# ESB32_with_USBC.net
KiCad netlist of a schematic drawn in Altium Designer
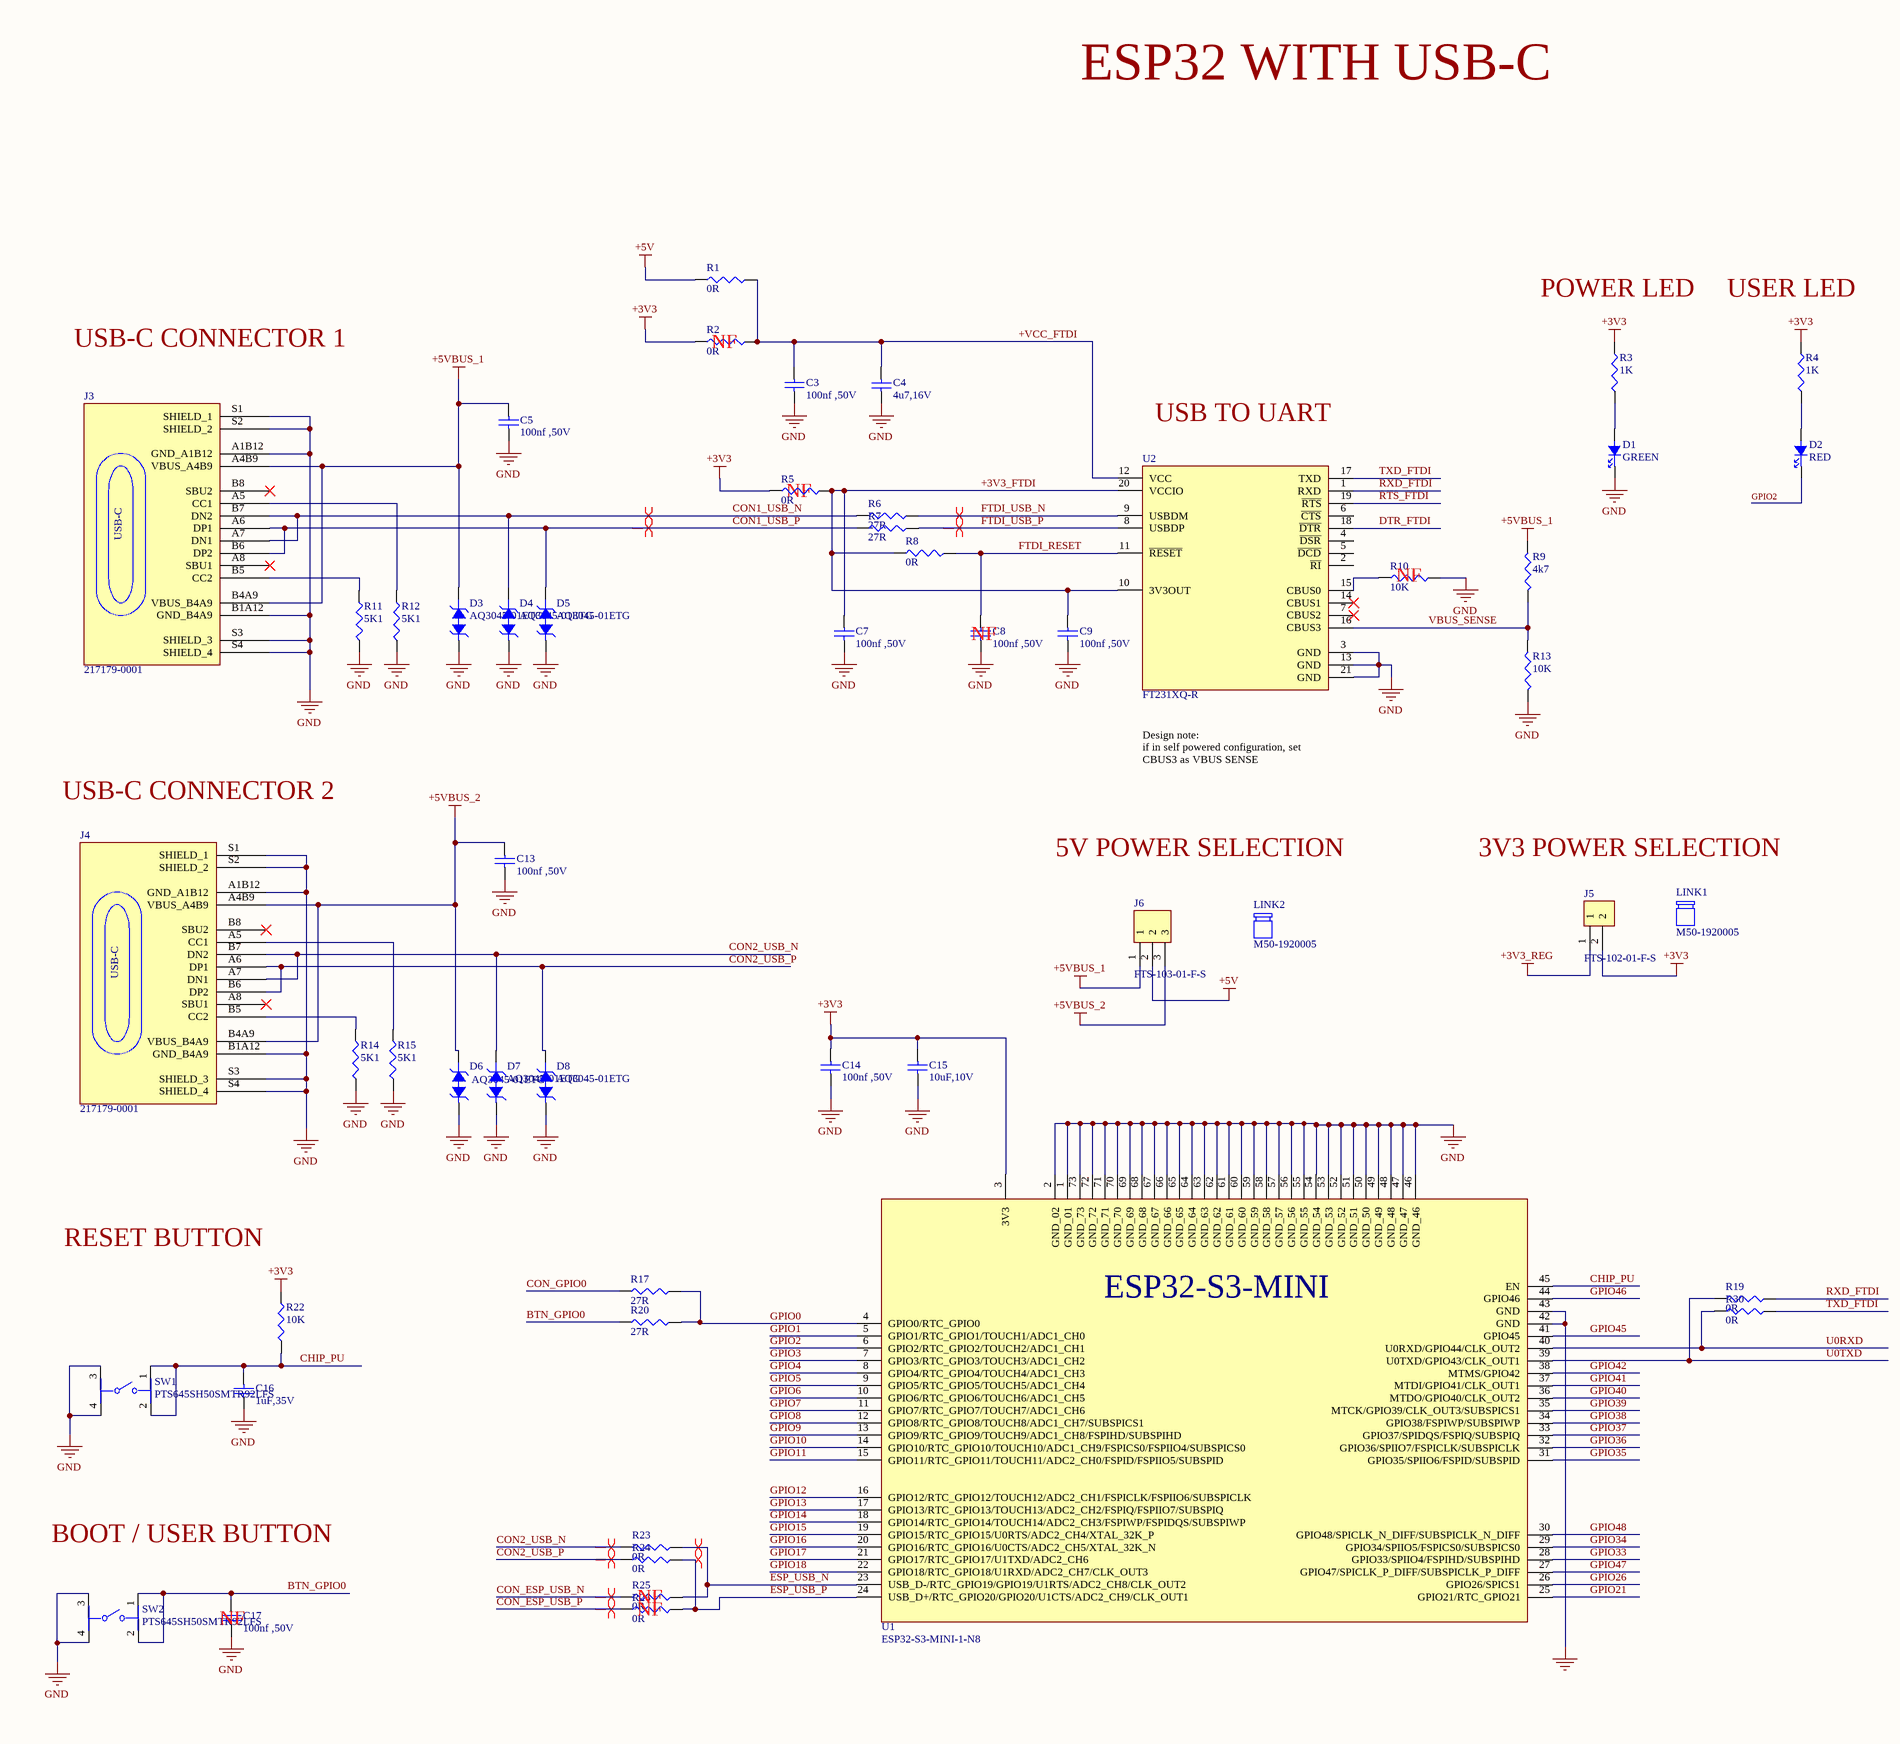
[diagram p0: ESB32 with USBC.SchDoc, left]
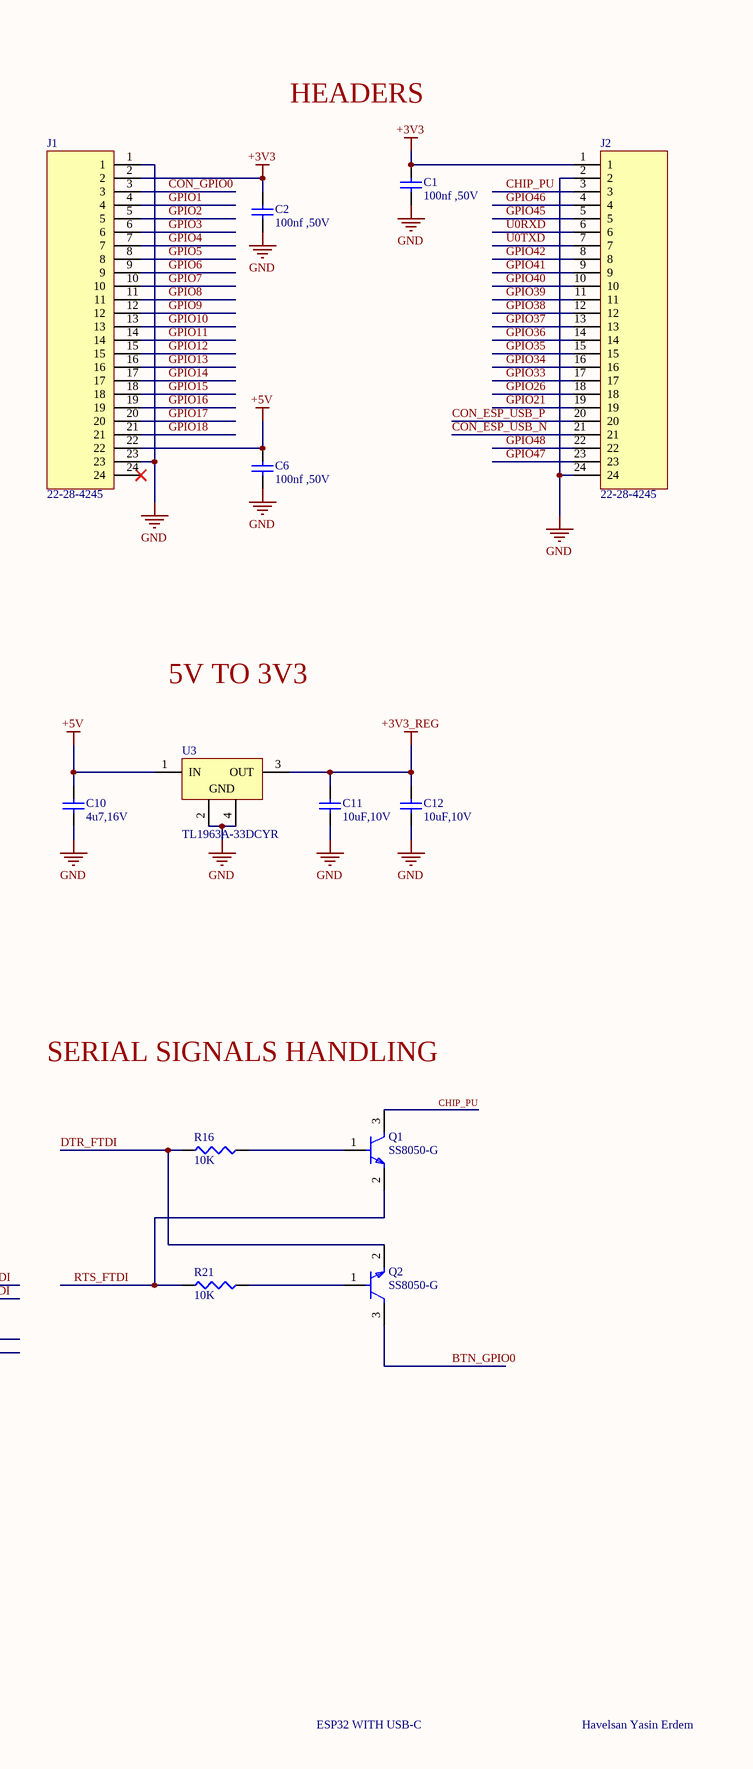
[diagram p1: ESB32 with USBC.SchDoc, right]

(export (version "E")
  (design (tool "Eeschema 10.0.6"))
  (components
    (comp (ref "C1")
      (value "100nf ,50V")
      (footprint "CAPC1005X55N")
      (description "CAP CER 0.1UF 50V X7R 0402")
      (fields
        (field (name "MANUFACTURER") "Samsung")
        (field (name "MANUFACTURER PART NUMBER") "CL05B104KB54PNC")
      )
      (libsource (lib "Schlib") (part "CL05B104KB54PNC"))
    )
    (comp (ref "C2")
      (value "100nf ,50V")
      (footprint "CAPC1005X55N")
      (description "CAP CER 0.1UF 50V X7R 0402")
      (fields
        (field (name "MANUFACTURER") "Samsung")
        (field (name "MANUFACTURER PART NUMBER") "CL05B104KB54PNC")
      )
      (libsource (lib "Schlib") (part "CL05B104KB54PNC"))
    )
    (comp (ref "C3")
      (value "100nf ,50V")
      (footprint "CAPC1005X55N")
      (description "CAP CER 0.1UF 50V X7R 0402")
      (fields
        (field (name "MANUFACTURER") "Samsung")
        (field (name "MANUFACTURER PART NUMBER") "CL05B104KB54PNC")
      )
      (libsource (lib "Schlib") (part "CL05B104KB54PNC"))
    )
    (comp (ref "C4")
      (value "4u7,16V")
      (footprint "CAPC1005X55N")
      (description "CAP CER 4.7UF 16V X5R 0402")
      (fields
        (field (name "MANUFACTURER") "Samsung")
        (field (name "MANUFACTURER PART NUMBER") "CL05A475MO5NUNC")
      )
      (libsource (lib "Schlib") (part "CL05A475MO5NUNC"))
    )
    (comp (ref "C5")
      (value "100nf ,50V")
      (footprint "CAPC1005X55N")
      (description "CAP CER 0.1UF 50V X7R 0402")
      (fields
        (field (name "MANUFACTURER") "Samsung")
        (field (name "MANUFACTURER PART NUMBER") "CL05B104KB54PNC")
      )
      (libsource (lib "Schlib") (part "CL05B104KB54PNC"))
    )
    (comp (ref "C6")
      (value "100nf ,50V")
      (footprint "CAPC1005X55N")
      (description "CAP CER 0.1UF 50V X7R 0402")
      (fields
        (field (name "MANUFACTURER") "Samsung")
        (field (name "MANUFACTURER PART NUMBER") "CL05B104KB54PNC")
      )
      (libsource (lib "Schlib") (part "CL05B104KB54PNC"))
    )
    (comp (ref "C7")
      (value "100nf ,50V")
      (footprint "CAPC1005X55N")
      (description "CAP CER 0.1UF 50V X7R 0402")
      (fields
        (field (name "MANUFACTURER") "Samsung")
        (field (name "MANUFACTURER PART NUMBER") "CL05B104KB54PNC")
      )
      (libsource (lib "Schlib") (part "CL05B104KB54PNC"))
    )
    (comp (ref "C8")
      (value "100nf ,50V")
      (footprint "CAPC1005X55N")
      (description "CAP CER 0.1UF 50V X7R 0402")
      (fields
        (field (name "MANUFACTURER") "Samsung")
        (field (name "MANUFACTURER PART NUMBER") "CL05B104KB54PNC")
      )
      (libsource (lib "Schlib") (part "CL05B104KB54PNC"))
    )
    (comp (ref "C9")
      (value "100nf ,50V")
      (footprint "CAPC1005X55N")
      (description "CAP CER 0.1UF 50V X7R 0402")
      (fields
        (field (name "MANUFACTURER") "Samsung")
        (field (name "MANUFACTURER PART NUMBER") "CL05B104KB54PNC")
      )
      (libsource (lib "Schlib") (part "CL05B104KB54PNC"))
    )
    (comp (ref "C10")
      (value "4u7,16V")
      (footprint "CAPC1005X55N")
      (description "CAP CER 4.7UF 16V X5R 0402")
      (fields
        (field (name "MANUFACTURER") "Samsung")
        (field (name "MANUFACTURER PART NUMBER") "CL05A475MO5NUNC")
      )
      (libsource (lib "Schlib") (part "CL05A475MO5NUNC"))
    )
    (comp (ref "C11")
      (value "10uF,10V")
      (footprint "CAPC1005X55N")
      (description "CAP CER 10UF 10V X5R 0402")
      (fields
        (field (name "MANUFACTURER") "Samsung")
        (field (name "MANUFACTURER PART NUMBER") "CL05A106MP8NUB8")
      )
      (libsource (lib "Schlib") (part "CL05A106MP8NUB8"))
    )
    (comp (ref "C12")
      (value "10uF,10V")
      (footprint "CAPC1005X55N")
      (description "CAP CER 10UF 10V X5R 0402")
      (fields
        (field (name "MANUFACTURER") "Samsung")
        (field (name "MANUFACTURER PART NUMBER") "CL05A106MP8NUB8")
      )
      (libsource (lib "Schlib") (part "CL05A106MP8NUB8"))
    )
    (comp (ref "C13")
      (value "100nf ,50V")
      (footprint "CAPC1005X55N")
      (description "CAP CER 0.1UF 50V X7R 0402")
      (fields
        (field (name "MANUFACTURER") "Samsung")
        (field (name "MANUFACTURER PART NUMBER") "CL05B104KB54PNC")
      )
      (libsource (lib "Schlib") (part "CL05B104KB54PNC"))
    )
    (comp (ref "C14")
      (value "100nf ,50V")
      (footprint "CAPC1005X55N")
      (description "CAP CER 0.1UF 50V X7R 0402")
      (fields
        (field (name "MANUFACTURER") "Samsung")
        (field (name "MANUFACTURER PART NUMBER") "CL05B104KB54PNC")
      )
      (libsource (lib "Schlib") (part "CL05B104KB54PNC"))
    )
    (comp (ref "C15")
      (value "10uF,10V")
      (footprint "CAPC1005X55N")
      (description "CAP CER 10UF 10V X5R 0402")
      (fields
        (field (name "MANUFACTURER") "Samsung")
        (field (name "MANUFACTURER PART NUMBER") "CL05A106MP8NUB8")
      )
      (libsource (lib "Schlib") (part "CL05A106MP8NUB8"))
    )
    (comp (ref "C16")
      (value "1uF,35V")
      (footprint "CAPC1005X55N")
      (description "CAP CER 1UF 35V X5R 0402")
      (fields
        (field (name "MANUFACTURER") "Samsung")
        (field (name "MANUFACTURER PART NUMBER") "CL05A105KL5NRNC")
      )
      (libsource (lib "Schlib") (part "CL05A105KL5NRNC"))
    )
    (comp (ref "C17")
      (value "100nf ,50V")
      (footprint "CAPC1005X55N")
      (description "CAP CER 0.1UF 50V X7R 0402")
      (fields
        (field (name "MANUFACTURER") "Samsung")
        (field (name "MANUFACTURER PART NUMBER") "CL05B104KB54PNC")
      )
      (libsource (lib "Schlib") (part "CL05B104KB54PNC"))
    )
    (comp (ref "D1")
      (value "GREEN")
      (footprint "LED402G")
      (description "LED GREEN 0402 SMD")
      (fields
        (field (name "MANUFACTURER") "Vishay")
        (field (name "MANUFACTURER PART NUMBER") "VLMTG1500-GS08")
      )
      (libsource (lib "Schlib") (part "VLMTG1500-GS08"))
    )
    (comp (ref "D2")
      (value "RED")
      (footprint "LED402R")
      (description "LED RED 0402 SMD")
      (fields
        (field (name "MANUFACTURER") "Vishay")
        (field (name "MANUFACTURER PART NUMBER") "VLMS1500-GS08")
      )
      (libsource (lib "Schlib") (part "VLMS1500-GS08"))
    )
    (comp (ref "D3")
      (value "AQ3045-01ETG")
      (footprint "SOD882")
      (description "TVS DIODE 5.3VWM 12VC SOD882")
      (fields (field (name "MANUFACTURER") "Littelfuse") (field (name "LCSC PART NUMBER") "C3710326"))
      (libsource (lib "Schlib") (part "AQ3045-01ETG"))
    )
    (comp (ref "D4")
      (value "AQ3045-01ETG")
      (footprint "SOD882")
      (description "TVS DIODE 5.3VWM 12VC SOD882")
      (fields (field (name "MANUFACTURER") "Littelfuse") (field (name "LCSC PART NUMBER") "C3710326"))
      (libsource (lib "Schlib") (part "AQ3045-01ETG"))
    )
    (comp (ref "D5")
      (value "AQ3045-01ETG")
      (footprint "SOD882")
      (description "TVS DIODE 5.3VWM 12VC SOD882")
      (fields (field (name "MANUFACTURER") "Littelfuse") (field (name "LCSC PART NUMBER") "C3710326"))
      (libsource (lib "Schlib") (part "AQ3045-01ETG"))
    )
    (comp (ref "D6")
      (value "AQ3045-01ETG")
      (footprint "SOD882")
      (description "TVS DIODE 5.3VWM 12VC SOD882")
      (fields (field (name "MANUFACTURER") "Littelfuse") (field (name "LCSC PART NUMBER") "C3710326"))
      (libsource (lib "Schlib") (part "AQ3045-01ETG"))
    )
    (comp (ref "D7")
      (value "AQ3045-01ETG")
      (footprint "SOD882")
      (description "TVS DIODE 5.3VWM 12VC SOD882")
      (fields (field (name "MANUFACTURER") "Littelfuse") (field (name "LCSC PART NUMBER") "C3710326"))
      (libsource (lib "Schlib") (part "AQ3045-01ETG"))
    )
    (comp (ref "D8")
      (value "AQ3045-01ETG")
      (footprint "SOD882")
      (description "TVS DIODE 5.3VWM 12VC SOD882")
      (fields (field (name "MANUFACTURER") "Littelfuse") (field (name "LCSC PART NUMBER") "C3710326"))
      (libsource (lib "Schlib") (part "AQ3045-01ETG"))
    )
    (comp (ref "J1")
      (value "22-28-4245")
      (footprint "HDR_1x24_2.54MM")
      (description "CONN HEADER VERT 24POS 2.54MM")
      (fields (field (name "MANUFACTURER") "Molex") (field (name "LCSC PART NUMBER") "C7145888"))
      (libsource (lib "") (part "22-28-4245_1"))
    )
    (comp (ref "J2")
      (value "22-28-4245")
      (footprint "HDR_1x24_2.54MM")
      (description "CONN HEADER VERT 24POS 2.54MM")
      (fields (field (name "MANUFACTURER") "Molex") (field (name "LCSC PART NUMBER") "C7145888"))
      (libsource (lib "Schlib") (part "22-28-4245"))
    )
    (comp (ref "J3")
      (value "217179-0001")
      (footprint "FP-2171790001-MFG")
      (description "CONN RCP USB2.0 TYP C 24P SMD RA")
      (fields (field (name "MANUFACTURER") "Molex") (field (name "LCSC PART NUMBER") "C138021"))
      (libsource (lib "Schlib") (part "217179-0001"))
    )
    (comp (ref "J4")
      (value "217179-0001")
      (footprint "FP-2171790001-MFG")
      (description "CONN RCP USB2.0 TYP C 24P SMD RA")
      (fields (field (name "MANUFACTURER") "Molex") (field (name "LCSC PART NUMBER") "C138021"))
      (libsource (lib "Schlib") (part "217179-0001"))
    )
    (comp (ref "J5")
      (value "FTS-102-01-F-S")
      (footprint "HDR_1x2_1.27MM")
      (description "CONN HEADER VERT 2POS 1.27MM")
      (fields (field (name "MANUFACTURER") "Samtec") (field (name "LCSC PART NUMBER") "C6045317"))
      (libsource (lib "Schlib") (part "FTS-102-01-F-S"))
    )
    (comp (ref "J6")
      (value "FTS-103-01-F-S")
      (footprint "HDR_1x3_1.27MM")
      (description "CONN HEADER VERT 3POS 1.27MM")
      (fields (field (name "MANUFACTURER") "Samtec") (field (name "LCSC PART NUMBER") "C3333578"))
      (libsource (lib "Schlib") (part "FTS-103-01-F-S"))
    )
    (comp (ref "LINK1")
      (value "M50-1920005")
      (description "CONN SHUNT 1.27MM RED")
      (fields (field (name "MANUFACTURER") "Harwin") (field (name "LCSC PART NUMBER") "C6985646"))
      (libsource (lib "Schlib") (part "M50-1920005"))
    )
    (comp (ref "LINK2")
      (value "M50-1920005")
      (description "CONN SHUNT 1.27MM RED")
      (fields (field (name "MANUFACTURER") "Harwin") (field (name "LCSC PART NUMBER") "C6985646"))
      (libsource (lib "Schlib") (part "M50-1920005"))
    )
    (comp (ref "Q1")
      (value "SS8050-G")
      (footprint "FP-SS8050-G-IPC_B")
      (description "TRANS NPN 25V 1.5A SOT-23-3")
      (fields (field (name "MANUFACTURER") "Comchip") (field (name "LCSC PART NUMBER") "C164886"))
      (libsource (lib "Schlib") (part "SS8050-G"))
    )
    (comp (ref "Q2")
      (value "SS8050-G")
      (footprint "FP-SS8050-G-IPC_B")
      (description "TRANS NPN 25V 1.5A SOT-23-3")
      (fields (field (name "MANUFACTURER") "Comchip") (field (name "LCSC PART NUMBER") "C164886"))
      (libsource (lib "Schlib") (part "SS8050-G"))
    )
    (comp (ref "R1")
      (value "0R")
      (footprint "RESC1005X37N")
      (description "RES SMD 0 OHM JUMPER 1/16W 0402")
      (fields
        (field (name "MANUFACTURER") "Yageo")
        (field (name "MANUFACTURER PART NUMBER") "AC0402JR-070RL")
      )
      (libsource (lib "Schlib") (part "AC0402JR-070RL"))
    )
    (comp (ref "R2")
      (value "0R")
      (footprint "RESC1005X37N")
      (description "RES SMD 0 OHM JUMPER 1/16W 0402")
      (fields
        (field (name "MANUFACTURER") "Yageo")
        (field (name "MANUFACTURER PART NUMBER") "AC0402JR-070RL")
      )
      (libsource (lib "Schlib") (part "AC0402JR-070RL"))
    )
    (comp (ref "R3")
      (value "1K")
      (footprint "RESC1005X37N")
      (description "RES 1K OHM 1% 1/16W 0402")
      (fields
        (field (name "MANUFACTURER") "Yageo")
        (field (name "MANUFACTURER PART NUMBER") "RC0402FR-071KL")
      )
      (libsource (lib "Schlib") (part "RC0402FR-071KL"))
    )
    (comp (ref "R4")
      (value "1K")
      (footprint "RESC1005X37N")
      (description "RES 1K OHM 1% 1/16W 0402")
      (fields
        (field (name "MANUFACTURER") "Yageo")
        (field (name "MANUFACTURER PART NUMBER") "RC0402FR-071KL")
      )
      (libsource (lib "Schlib") (part "RC0402FR-071KL"))
    )
    (comp (ref "R5")
      (value "0R")
      (footprint "RESC1005X37N")
      (description "RES SMD 0 OHM JUMPER 1/16W 0402")
      (fields
        (field (name "MANUFACTURER") "Yageo")
        (field (name "MANUFACTURER PART NUMBER") "AC0402JR-070RL")
      )
      (libsource (lib "Schlib") (part "AC0402JR-070RL"))
    )
    (comp (ref "R6")
      (value "27R")
      (footprint "RESC1005X37N")
      (description "RES 27 OHM 1% 1/16W 0402")
      (fields
        (field (name "MANUFACTURER") "Yageo")
        (field (name "MANUFACTURER PART NUMBER") "RC0402FR-0727RL")
      )
      (libsource (lib "Schlib") (part "RC0402FR-0727RL"))
    )
    (comp (ref "R7")
      (value "27R")
      (footprint "RESC1005X37N")
      (description "RES 27 OHM 1% 1/16W 0402")
      (fields
        (field (name "MANUFACTURER") "Yageo")
        (field (name "MANUFACTURER PART NUMBER") "RC0402FR-0727RL")
      )
      (libsource (lib "Schlib") (part "RC0402FR-0727RL"))
    )
    (comp (ref "R8")
      (value "0R")
      (footprint "RESC1005X37N")
      (description "RES SMD 0 OHM JUMPER 1/16W 0402")
      (fields
        (field (name "MANUFACTURER") "Yageo")
        (field (name "MANUFACTURER PART NUMBER") "AC0402JR-070RL")
      )
      (libsource (lib "Schlib") (part "AC0402JR-070RL"))
    )
    (comp (ref "R9")
      (value "4k7")
      (footprint "RESC1005X37N")
      (description "RES 4.7K OHM 1% 1/16W 0402")
      (fields
        (field (name "MANUFACTURER") "Yageo")
        (field (name "MANUFACTURER PART NUMBER") "RC0402FR-074K7L")
      )
      (libsource (lib "Schlib") (part "RC0402FR-074K7L"))
    )
    (comp (ref "R10")
      (value "10K")
      (footprint "RESC1005X37N")
      (description "RES SMD 10K OHM 1% 1/16W 0402")
      (fields
        (field (name "MANUFACTURER") "Yageo")
        (field (name "MANUFACTURER PART NUMBER") "AC0402FR-0710KL")
      )
      (libsource (lib "Schlib") (part "AC0402FR-0710KL"))
    )
    (comp (ref "R11")
      (value "5K1")
      (footprint "RESC1005X37N")
      (description "RES SMD 5.1K OHM 1% 1/16W 0402")
      (fields
        (field (name "MANUFACTURER") "Yageo")
        (field (name "MANUFACTURER PART NUMBER") "AC0402FR-075K1L")
      )
      (libsource (lib "Schlib") (part "AC0402FR-075K1L"))
    )
    (comp (ref "R12")
      (value "5K1")
      (footprint "RESC1005X37N")
      (description "RES SMD 5.1K OHM 1% 1/16W 0402")
      (fields
        (field (name "MANUFACTURER") "Yageo")
        (field (name "MANUFACTURER PART NUMBER") "AC0402FR-075K1L")
      )
      (libsource (lib "Schlib") (part "AC0402FR-075K1L"))
    )
    (comp (ref "R13")
      (value "10K")
      (footprint "RESC1005X37N")
      (description "RES SMD 10K OHM 1% 1/16W 0402")
      (fields
        (field (name "MANUFACTURER") "Yageo")
        (field (name "MANUFACTURER PART NUMBER") "AC0402FR-0710KL")
      )
      (libsource (lib "Schlib") (part "AC0402FR-0710KL"))
    )
    (comp (ref "R14")
      (value "5K1")
      (footprint "RESC1005X37N")
      (description "RES SMD 5.1K OHM 1% 1/16W 0402")
      (fields
        (field (name "MANUFACTURER") "Yageo")
        (field (name "MANUFACTURER PART NUMBER") "AC0402FR-075K1L")
      )
      (libsource (lib "Schlib") (part "AC0402FR-075K1L"))
    )
    (comp (ref "R15")
      (value "5K1")
      (footprint "RESC1005X37N")
      (description "RES SMD 5.1K OHM 1% 1/16W 0402")
      (fields
        (field (name "MANUFACTURER") "Yageo")
        (field (name "MANUFACTURER PART NUMBER") "AC0402FR-075K1L")
      )
      (libsource (lib "Schlib") (part "AC0402FR-075K1L"))
    )
    (comp (ref "R16")
      (value "10K")
      (footprint "RESC1005X37N")
      (description "RES SMD 10K OHM 1% 1/16W 0402")
      (fields
        (field (name "MANUFACTURER") "Yageo")
        (field (name "MANUFACTURER PART NUMBER") "AC0402FR-0710KL")
      )
      (libsource (lib "Schlib") (part "AC0402FR-0710KL"))
    )
    (comp (ref "R17")
      (value "27R")
      (footprint "RESC1005X37N")
      (description "RES 27 OHM 1% 1/16W 0402")
      (fields
        (field (name "MANUFACTURER") "Yageo")
        (field (name "MANUFACTURER PART NUMBER") "RC0402FR-0727RL")
      )
      (libsource (lib "Schlib") (part "RC0402FR-0727RL"))
    )
    (comp (ref "R19")
      (value "0R")
      (footprint "RESC1005X37N")
      (description "RES SMD 0 OHM JUMPER 1/16W 0402")
      (fields
        (field (name "MANUFACTURER") "Yageo")
        (field (name "MANUFACTURER PART NUMBER") "AC0402JR-070RL")
      )
      (libsource (lib "Schlib") (part "AC0402JR-070RL"))
    )
    (comp (ref "R20")
      (value "27R")
      (footprint "RESC1005X37N")
      (description "RES 27 OHM 1% 1/16W 0402")
      (fields
        (field (name "MANUFACTURER") "Yageo")
        (field (name "MANUFACTURER PART NUMBER") "RC0402FR-0727RL")
      )
      (libsource (lib "Schlib") (part "RC0402FR-0727RL"))
    )
    (comp (ref "R21")
      (value "10K")
      (footprint "RESC1005X37N")
      (description "RES SMD 10K OHM 1% 1/16W 0402")
      (fields
        (field (name "MANUFACTURER") "Yageo")
        (field (name "MANUFACTURER PART NUMBER") "AC0402FR-0710KL")
      )
      (libsource (lib "Schlib") (part "AC0402FR-0710KL"))
    )
    (comp (ref "R22")
      (value "10K")
      (footprint "RESC1005X37N")
      (description "RES SMD 10K OHM 1% 1/16W 0402")
      (fields
        (field (name "MANUFACTURER") "Yageo")
        (field (name "MANUFACTURER PART NUMBER") "AC0402FR-0710KL")
      )
      (libsource (lib "Schlib") (part "AC0402FR-0710KL"))
    )
    (comp (ref "R23")
      (value "0R")
      (footprint "RESC1005X37N")
      (description "RES SMD 0 OHM JUMPER 1/16W 0402")
      (fields
        (field (name "MANUFACTURER") "Yageo")
        (field (name "MANUFACTURER PART NUMBER") "AC0402JR-070RL")
      )
      (libsource (lib "Schlib") (part "AC0402JR-070RL"))
    )
    (comp (ref "R24")
      (value "0R")
      (footprint "RESC1005X37N")
      (description "RES SMD 0 OHM JUMPER 1/16W 0402")
      (fields
        (field (name "MANUFACTURER") "Yageo")
        (field (name "MANUFACTURER PART NUMBER") "AC0402JR-070RL")
      )
      (libsource (lib "Schlib") (part "AC0402JR-070RL"))
    )
    (comp (ref "R25")
      (value "0R")
      (footprint "RESC1005X37N")
      (description "RES SMD 0 OHM JUMPER 1/16W 0402")
      (fields
        (field (name "MANUFACTURER") "Yageo")
        (field (name "MANUFACTURER PART NUMBER") "AC0402JR-070RL")
      )
      (libsource (lib "Schlib") (part "AC0402JR-070RL"))
    )
    (comp (ref "R26")
      (value "0R")
      (footprint "RESC1005X37N")
      (description "RES SMD 0 OHM JUMPER 1/16W 0402")
      (fields
        (field (name "MANUFACTURER") "Yageo")
        (field (name "MANUFACTURER PART NUMBER") "AC0402JR-070RL")
      )
      (libsource (lib "Schlib") (part "AC0402JR-070RL"))
    )
    (comp (ref "R30")
      (value "0R")
      (footprint "RESC1005X37N")
      (description "RES SMD 0 OHM JUMPER 1/16W 0402")
      (fields
        (field (name "MANUFACTURER") "Yageo")
        (field (name "MANUFACTURER PART NUMBER") "AC0402JR-070RL")
      )
      (libsource (lib "Schlib") (part "AC0402JR-070RL"))
    )
    (comp (ref "SW1")
      (value "PTS645SH50SMTR92LFS")
      (footprint "FP-PTS645SH50SMTR92LFS-MFG")
      (description "SWITCH TACTILE SPST-NO 0.05A 12V")
      (fields (field (name "MANUFACTURER") "ITT C&K") (field (name "LCSC PART NUMBER") "C221869"))
      (libsource (lib "Schlib") (part "PTS645SH50SMTR92LFS"))
    )
    (comp (ref "SW2")
      (value "PTS645SH50SMTR92LFS")
      (footprint "FP-PTS645SH50SMTR92LFS-MFG")
      (description "SWITCH TACTILE SPST-NO 0.05A 12V")
      (fields (field (name "MANUFACTURER") "ITT C&K") (field (name "LCSC PART NUMBER") "C221869"))
      (libsource (lib "Schlib") (part "PTS645SH50SMTR92LFS"))
    )
    (comp (ref "U1")
      (value "ESP32-S3-MINI-1-N8")
      (footprint "XCVR_ESP32-S3-MINI-1-N8")
      (description "SMD Module, ESP32-S3FN8, 8 mb Sp")
      (fields (field (name "MANUFACTURER") "Espressif Systems") (field (name "LCSC PART NUMBER") "C2913206"))
      (libsource (lib "Schlib") (part "ESP32-S3-MINI-1-N8_1"))
    )
    (comp (ref "U2")
      (value "FT231XQ-R")
      (footprint "FP-QFN-20-IPC_B")
      (description "IC USB SERIAL FULL UART 20QFN")
      (fields (field (name "MANUFACTURER") "FTDI") (field (name "LCSC PART NUMBER") "C132159"))
      (libsource (lib "Schlib") (part "FT231XQ-R"))
    )
    (comp (ref "U3")
      (value "TL1963A-33DCYR")
      (footprint "DCY0004A_N")
      (description "IC REG LIN 3.3V 1.5A SOT-223-4")
      (fields (field (name "MANUFACTURER") "Texas Instruments") (field (name "LCSC PART NUMBER") "C181262"))
      (libsource (lib "Schlib") (part "TL1963A-33DCYR"))
    )
  )
  (nets
    (net (code "1") (name "+3V3") (class "Default")
      (node (ref "C1") (pin "1") (pinfunction "1_1") (pintype "passive"))
      (node (ref "C14") (pin "1") (pinfunction "1_1") (pintype "passive"))
      (node (ref "C15") (pin "1") (pinfunction "1_1") (pintype "passive"))
      (node (ref "C2") (pin "1") (pinfunction "1_1") (pintype "passive"))
      (node (ref "J1") (pin "2") (pinfunction "2_2") (pintype "passive"))
      (node (ref "J2") (pin "1") (pinfunction "1_1") (pintype "passive"))
      (node (ref "J5") (pin "2") (pinfunction "2_2") (pintype "passive"))
      (node (ref "R2") (pin "1") (pinfunction "1_1") (pintype "passive"))
      (node (ref "R22") (pin "2") (pinfunction "2_2") (pintype "passive"))
      (node (ref "R3") (pin "2") (pinfunction "2_2") (pintype "passive"))
      (node (ref "R4") (pin "2") (pinfunction "2_2") (pintype "passive"))
      (node (ref "R5") (pin "1") (pinfunction "1_1") (pintype "passive"))
      (node (ref "U1") (pin "3") (pinfunction "3V3_3") (pintype "passive"))
    )
    (net (code "2") (name "+3V3_REG") (class "Default")
      (node (ref "C11") (pin "1") (pinfunction "1_1") (pintype "passive"))
      (node (ref "C12") (pin "1") (pinfunction "1_1") (pintype "passive"))
      (node (ref "J5") (pin "1") (pinfunction "1_1") (pintype "passive"))
      (node (ref "U3") (pin "3") (pinfunction "OUT_3") (pintype "power_in"))
    )
    (net (code "3") (name "+5V") (class "Default")
      (node (ref "C10") (pin "2") (pinfunction "2_2") (pintype "passive"))
      (node (ref "C6") (pin "1") (pinfunction "1_1") (pintype "passive"))
      (node (ref "J1") (pin "22") (pinfunction "22_22") (pintype "passive"))
      (node (ref "J6") (pin "2") (pinfunction "2_2") (pintype "passive"))
      (node (ref "R1") (pin "1") (pinfunction "1_1") (pintype "passive"))
      (node (ref "U3") (pin "1") (pinfunction "IN_1") (pintype "power_in"))
    )
    (net (code "4") (name "+5VBUS_1") (class "Default")
      (node (ref "C5") (pin "1") (pinfunction "1_1") (pintype "passive"))
      (node (ref "D3") (pin "2") (pinfunction "2_2") (pintype "passive"))
      (node (ref "J3") (pin "A4B9") (pinfunction "VBUS_A4B9_A4B9") (pintype "passive"))
      (node (ref "J3") (pin "B4A9") (pinfunction "VBUS_B4A9_B4A9") (pintype "passive"))
      (node (ref "J6") (pin "1") (pinfunction "1_1") (pintype "passive"))
      (node (ref "R9") (pin "1") (pinfunction "1_1") (pintype "passive"))
    )
    (net (code "5") (name "+5VBUS_2") (class "Default")
      (node (ref "C13") (pin "1") (pinfunction "1_1") (pintype "passive"))
      (node (ref "D6") (pin "2") (pinfunction "2_2") (pintype "passive"))
      (node (ref "J4") (pin "A4B9") (pinfunction "VBUS_A4B9_A4B9") (pintype "passive"))
      (node (ref "J4") (pin "B4A9") (pinfunction "VBUS_B4A9_B4A9") (pintype "passive"))
      (node (ref "J6") (pin "3") (pinfunction "3_3") (pintype "passive"))
    )
    (net (code "6") (name "/+3V3_FTDI") (class "Default")
      (node (ref "C7") (pin "1") (pinfunction "1_1") (pintype "passive"))
      (node (ref "C9") (pin "1") (pinfunction "1_1") (pintype "passive"))
      (node (ref "R5") (pin "2") (pinfunction "2_2") (pintype "passive"))
      (node (ref "R8") (pin "1") (pinfunction "1_1") (pintype "passive"))
      (node (ref "U2") (pin "10") (pinfunction "3V3OUT_10") (pintype "passive"))
      (node (ref "U2") (pin "20") (pinfunction "VCCIO_20") (pintype "passive"))
    )
    (net (code "7") (name "/+VCC_FTDI") (class "Default")
      (node (ref "C3") (pin "1") (pinfunction "1_1") (pintype "passive"))
      (node (ref "C4") (pin "2") (pinfunction "2_2") (pintype "passive"))
      (node (ref "R1") (pin "2") (pinfunction "2_2") (pintype "passive"))
      (node (ref "R2") (pin "2") (pinfunction "2_2") (pintype "passive"))
      (node (ref "U2") (pin "12") (pinfunction "VCC_12") (pintype "passive"))
    )
    (net (code "8") (name "/BTN_GPIO0") (class "Default")
      (node (ref "C17") (pin "1") (pinfunction "1_1") (pintype "passive"))
      (node (ref "Q2") (pin "3") (pinfunction "C_3") (pintype "passive"))
      (node (ref "R20") (pin "1") (pinfunction "1_1") (pintype "passive"))
      (node (ref "SW2") (pin "1") (pinfunction "1_1") (pintype "passive"))
      (node (ref "SW2") (pin "2") (pinfunction "2_2") (pintype "passive"))
    )
    (net (code "9") (name "/CHIP_PU") (class "Default")
      (node (ref "C16") (pin "2") (pinfunction "2_2") (pintype "passive"))
      (node (ref "J2") (pin "3") (pinfunction "3_3") (pintype "passive"))
      (node (ref "Q1") (pin "3") (pinfunction "C_3") (pintype "passive"))
      (node (ref "R22") (pin "1") (pinfunction "1_1") (pintype "passive"))
      (node (ref "SW1") (pin "1") (pinfunction "1_1") (pintype "passive"))
      (node (ref "SW1") (pin "2") (pinfunction "2_2") (pintype "passive"))
      (node (ref "U1") (pin "45") (pinfunction "EN_45") (pintype "passive"))
    )
    (net (code "10") (name "/CON1_USB_N") (class "Default")
      (node (ref "D4") (pin "2") (pinfunction "2_2") (pintype "passive"))
      (node (ref "J3") (pin "A7") (pinfunction "DN1_A7") (pintype "passive"))
      (node (ref "J3") (pin "B7") (pinfunction "DN2_B7") (pintype "passive"))
      (node (ref "R6") (pin "1") (pinfunction "1_1") (pintype "passive"))
    )
    (net (code "11") (name "/CON1_USB_P") (class "Default")
      (node (ref "D5") (pin "2") (pinfunction "2_2") (pintype "passive"))
      (node (ref "J3") (pin "A6") (pinfunction "DP1_A6") (pintype "passive"))
      (node (ref "J3") (pin "B6") (pinfunction "DP2_B6") (pintype "passive"))
      (node (ref "R7") (pin "1") (pinfunction "1_1") (pintype "passive"))
    )
    (net (code "12") (name "/CON2_USB_N") (class "Default")
      (node (ref "D7") (pin "2") (pinfunction "2_2") (pintype "passive"))
      (node (ref "J4") (pin "A7") (pinfunction "DN1_A7") (pintype "passive"))
      (node (ref "J4") (pin "B7") (pinfunction "DN2_B7") (pintype "passive"))
      (node (ref "R23") (pin "1") (pinfunction "1_1") (pintype "passive"))
    )
    (net (code "13") (name "/CON2_USB_P") (class "Default")
      (node (ref "D8") (pin "2") (pinfunction "2_2") (pintype "passive"))
      (node (ref "J4") (pin "A6") (pinfunction "DP1_A6") (pintype "passive"))
      (node (ref "J4") (pin "B6") (pinfunction "DP2_B6") (pintype "passive"))
      (node (ref "R24") (pin "1") (pinfunction "1_1") (pintype "passive"))
    )
    (net (code "14") (name "/CON_ESP_USB_N") (class "Default")
      (node (ref "J2") (pin "21") (pinfunction "21_21") (pintype "passive"))
      (node (ref "R25") (pin "1") (pinfunction "1_1") (pintype "passive"))
    )
    (net (code "15") (name "/CON_ESP_USB_P") (class "Default")
      (node (ref "J2") (pin "20") (pinfunction "20_20") (pintype "passive"))
      (node (ref "R26") (pin "1") (pinfunction "1_1") (pintype "passive"))
    )
    (net (code "16") (name "/CON_GPIO0") (class "Default")
      (node (ref "J1") (pin "3") (pinfunction "3_3") (pintype "passive"))
      (node (ref "R17") (pin "1") (pinfunction "1_1") (pintype "passive"))
    )
    (net (code "17") (name "/DTR_FTDI") (class "Default")
      (node (ref "Q2") (pin "2") (pinfunction "E_2") (pintype "passive"))
      (node (ref "R16") (pin "1") (pinfunction "1_1") (pintype "passive"))
      (node (ref "U2") (pin "18") (pinfunction "~{DTR}_18") (pintype "passive"))
    )
    (net (code "18") (name "/ESP_USB_N") (class "Default")
      (node (ref "R23") (pin "2") (pinfunction "2_2") (pintype "passive"))
      (node (ref "R25") (pin "2") (pinfunction "2_2") (pintype "passive"))
      (node (ref "U1") (pin "23") (pinfunction "USB_D-/RTC_GPIO19/GPIO19/U1RTS/ADC2_CH8/CLK_OUT2_23") (pintype "passive"))
    )
    (net (code "19") (name "/ESP_USB_P") (class "Default")
      (node (ref "R24") (pin "2") (pinfunction "2_2") (pintype "passive"))
      (node (ref "R26") (pin "2") (pinfunction "2_2") (pintype "passive"))
      (node (ref "U1") (pin "24") (pinfunction "USB_D+/RTC_GPIO20/GPIO20/U1CTS/ADC2_CH9/CLK_OUT1_24") (pintype "passive"))
    )
    (net (code "20") (name "/FTDI_RESET") (class "Default")
      (node (ref "C8") (pin "1") (pinfunction "1_1") (pintype "passive"))
      (node (ref "R8") (pin "2") (pinfunction "2_2") (pintype "passive"))
      (node (ref "U2") (pin "11") (pinfunction "~{RESET}_11") (pintype "passive"))
    )
    (net (code "21") (name "/FTDI_USB_N") (class "Default")
      (node (ref "R6") (pin "2") (pinfunction "2_2") (pintype "passive"))
      (node (ref "U2") (pin "9") (pinfunction "USBDM_9") (pintype "passive"))
    )
    (net (code "22") (name "/FTDI_USB_P") (class "Default")
      (node (ref "R7") (pin "2") (pinfunction "2_2") (pintype "passive"))
      (node (ref "U2") (pin "8") (pinfunction "USBDP_8") (pintype "passive"))
    )
    (net (code "23") (name "/GPIO0") (class "Default")
      (node (ref "R17") (pin "2") (pinfunction "2_2") (pintype "passive"))
      (node (ref "R20") (pin "2") (pinfunction "2_2") (pintype "passive"))
      (node (ref "U1") (pin "4") (pinfunction "GPIO0/RTC_GPIO0_4") (pintype "passive"))
    )
    (net (code "24") (name "/GPIO1") (class "Default")
      (node (ref "J1") (pin "4") (pinfunction "4_4") (pintype "passive"))
      (node (ref "U1") (pin "5") (pinfunction "GPIO1/RTC_GPIO1/TOUCH1/ADC1_CH0_5") (pintype "passive"))
    )
    (net (code "25") (name "/GPIO2") (class "Default")
      (node (ref "D2") (pin "1") (pinfunction "1_1") (pintype "passive"))
      (node (ref "J1") (pin "5") (pinfunction "5_5") (pintype "passive"))
      (node (ref "U1") (pin "6") (pinfunction "GPIO2/RTC_GPIO2/TOUCH2/ADC1_CH1_6") (pintype "passive"))
    )
    (net (code "26") (name "/GPIO3") (class "Default")
      (node (ref "J1") (pin "6") (pinfunction "6_6") (pintype "passive"))
      (node (ref "U1") (pin "7") (pinfunction "GPIO3/RTC_GPIO3/TOUCH3/ADC1_CH2_7") (pintype "passive"))
    )
    (net (code "27") (name "/GPIO4") (class "Default")
      (node (ref "J1") (pin "7") (pinfunction "7_7") (pintype "passive"))
      (node (ref "U1") (pin "8") (pinfunction "GPIO4/RTC_GPIO4/TOUCH4/ADC1_CH3_8") (pintype "passive"))
    )
    (net (code "28") (name "/GPIO5") (class "Default")
      (node (ref "J1") (pin "8") (pinfunction "8_8") (pintype "passive"))
      (node (ref "U1") (pin "9") (pinfunction "GPIO5/RTC_GPIO5/TOUCH5/ADC1_CH4_9") (pintype "passive"))
    )
    (net (code "29") (name "/GPIO6") (class "Default")
      (node (ref "J1") (pin "9") (pinfunction "9_9") (pintype "passive"))
      (node (ref "U1") (pin "10") (pinfunction "GPIO6/RTC_GPIO6/TOUCH6/ADC1_CH5_10") (pintype "passive"))
    )
    (net (code "30") (name "/GPIO7") (class "Default")
      (node (ref "J1") (pin "10") (pinfunction "10_10") (pintype "passive"))
      (node (ref "U1") (pin "11") (pinfunction "GPIO7/RTC_GPIO7/TOUCH7/ADC1_CH6_11") (pintype "passive"))
    )
    (net (code "31") (name "/GPIO8") (class "Default")
      (node (ref "J1") (pin "11") (pinfunction "11_11") (pintype "passive"))
      (node (ref "U1") (pin "12") (pinfunction "GPIO8/RTC_GPIO8/TOUCH8/ADC1_CH7/SUBSPICS1_12") (pintype "passive"))
    )
    (net (code "32") (name "/GPIO9") (class "Default")
      (node (ref "J1") (pin "12") (pinfunction "12_12") (pintype "passive"))
      (node (ref "U1") (pin "13") (pinfunction "GPIO9/RTC_GPIO9/TOUCH9/ADC1_CH8/FSPIHD/SUBSPIHD_13") (pintype "passive"))
    )
    (net (code "33") (name "/GPIO10") (class "Default")
      (node (ref "J1") (pin "13") (pinfunction "13_13") (pintype "passive"))
      (node (ref "U1") (pin "14") (pinfunction "GPIO10/RTC_GPIO10/TOUCH10/ADC1_CH9/FSPICS0/FSPIIO4/SUBSPICS0_14") (pintype "passive"))
    )
    (net (code "34") (name "/GPIO11") (class "Default")
      (node (ref "J1") (pin "14") (pinfunction "14_14") (pintype "passive"))
      (node (ref "U1") (pin "15") (pinfunction "GPIO11/RTC_GPIO11/TOUCH11/ADC2_CH0/FSPID/FSPIIO5/SUBSPID_15") (pintype "passive"))
    )
    (net (code "35") (name "/GPIO12") (class "Default")
      (node (ref "J1") (pin "15") (pinfunction "15_15") (pintype "passive"))
      (node (ref "U1") (pin "16") (pinfunction "GPIO12/RTC_GPIO12/TOUCH12/ADC2_CH1/FSPICLK/FSPIIO6/SUBSPICLK_16") (pintype "passive"))
    )
    (net (code "36") (name "/GPIO13") (class "Default")
      (node (ref "J1") (pin "16") (pinfunction "16_16") (pintype "passive"))
      (node (ref "U1") (pin "17") (pinfunction "GPIO13/RTC_GPIO13/TOUCH13/ADC2_CH2/FSPIQ/FSPIIO7/SUBSPIQ_17") (pintype "passive"))
    )
    (net (code "37") (name "/GPIO14") (class "Default")
      (node (ref "J1") (pin "17") (pinfunction "17_17") (pintype "passive"))
      (node (ref "U1") (pin "18") (pinfunction "GPIO14/RTC_GPIO14/TOUCH14/ADC2_CH3/FSPIWP/FSPIDQS/SUBSPIWP_18") (pintype "passive"))
    )
    (net (code "38") (name "/GPIO15") (class "Default")
      (node (ref "J1") (pin "18") (pinfunction "18_18") (pintype "passive"))
      (node (ref "U1") (pin "19") (pinfunction "GPIO15/RTC_GPIO15/U0RTS/ADC2_CH4/XTAL_32K_P_19") (pintype "passive"))
    )
    (net (code "39") (name "/GPIO16") (class "Default")
      (node (ref "J1") (pin "19") (pinfunction "19_19") (pintype "passive"))
      (node (ref "U1") (pin "20") (pinfunction "GPIO16/RTC_GPIO16/U0CTS/ADC2_CH5/XTAL_32K_N_20") (pintype "passive"))
    )
    (net (code "40") (name "/GPIO17") (class "Default")
      (node (ref "J1") (pin "20") (pinfunction "20_20") (pintype "passive"))
      (node (ref "U1") (pin "21") (pinfunction "GPIO17/RTC_GPIO17/U1TXD/ADC2_CH6_21") (pintype "passive"))
    )
    (net (code "41") (name "/GPIO18") (class "Default")
      (node (ref "J1") (pin "21") (pinfunction "21_21") (pintype "passive"))
      (node (ref "U1") (pin "22") (pinfunction "GPIO18/RTC_GPIO18/U1RXD/ADC2_CH7/CLK_OUT3_22") (pintype "passive"))
    )
    (net (code "42") (name "/GPIO21") (class "Default")
      (node (ref "J2") (pin "19") (pinfunction "19_19") (pintype "passive"))
      (node (ref "U1") (pin "25") (pinfunction "GPIO21/RTC_GPIO21_25") (pintype "passive"))
    )
    (net (code "43") (name "/GPIO26") (class "Default")
      (node (ref "J2") (pin "18") (pinfunction "18_18") (pintype "passive"))
      (node (ref "U1") (pin "26") (pinfunction "GPIO26/SPICS1_26") (pintype "passive"))
    )
    (net (code "44") (name "/GPIO33") (class "Default")
      (node (ref "J2") (pin "17") (pinfunction "17_17") (pintype "passive"))
      (node (ref "U1") (pin "28") (pinfunction "GPIO33/SPIIO4/FSPIHD/SUBSPIHD_28") (pintype "passive"))
    )
    (net (code "45") (name "/GPIO34") (class "Default")
      (node (ref "J2") (pin "16") (pinfunction "16_16") (pintype "passive"))
      (node (ref "U1") (pin "29") (pinfunction "GPIO34/SPIIO5/FSPICS0/SUBSPICS0_29") (pintype "passive"))
    )
    (net (code "46") (name "/GPIO35") (class "Default")
      (node (ref "J2") (pin "15") (pinfunction "15_15") (pintype "passive"))
      (node (ref "U1") (pin "31") (pinfunction "GPIO35/SPIIO6/FSPID/SUBSPID_31") (pintype "passive"))
    )
    (net (code "47") (name "/GPIO36") (class "Default")
      (node (ref "J2") (pin "14") (pinfunction "14_14") (pintype "passive"))
      (node (ref "U1") (pin "32") (pinfunction "GPIO36/SPIIO7/FSPICLK/SUBSPICLK_32") (pintype "passive"))
    )
    (net (code "48") (name "/GPIO37") (class "Default")
      (node (ref "J2") (pin "13") (pinfunction "13_13") (pintype "passive"))
      (node (ref "U1") (pin "33") (pinfunction "GPIO37/SPIDQS/FSPIQ/SUBSPIQ_33") (pintype "passive"))
    )
    (net (code "49") (name "/GPIO38") (class "Default")
      (node (ref "J2") (pin "12") (pinfunction "12_12") (pintype "passive"))
      (node (ref "U1") (pin "34") (pinfunction "GPIO38/FSPIWP/SUBSPIWP_34") (pintype "passive"))
    )
    (net (code "50") (name "/GPIO39") (class "Default")
      (node (ref "J2") (pin "11") (pinfunction "11_11") (pintype "passive"))
      (node (ref "U1") (pin "35") (pinfunction "MTCK/GPIO39/CLK_OUT3/SUBSPICS1_35") (pintype "passive"))
    )
    (net (code "51") (name "/GPIO40") (class "Default")
      (node (ref "J2") (pin "10") (pinfunction "10_10") (pintype "passive"))
      (node (ref "U1") (pin "36") (pinfunction "MTDO/GPIO40/CLK_OUT2_36") (pintype "passive"))
    )
    (net (code "52") (name "/GPIO41") (class "Default")
      (node (ref "J2") (pin "9") (pinfunction "9_9") (pintype "passive"))
      (node (ref "U1") (pin "37") (pinfunction "MTDI/GPIO41/CLK_OUT1_37") (pintype "passive"))
    )
    (net (code "53") (name "/GPIO42") (class "Default")
      (node (ref "J2") (pin "8") (pinfunction "8_8") (pintype "passive"))
      (node (ref "U1") (pin "38") (pinfunction "MTMS/GPIO42_38") (pintype "passive"))
    )
    (net (code "54") (name "/GPIO45") (class "Default")
      (node (ref "J2") (pin "5") (pinfunction "5_5") (pintype "passive"))
      (node (ref "U1") (pin "41") (pinfunction "GPIO45_41") (pintype "passive"))
    )
    (net (code "55") (name "/GPIO46") (class "Default")
      (node (ref "J2") (pin "4") (pinfunction "4_4") (pintype "passive"))
      (node (ref "U1") (pin "44") (pinfunction "GPIO46_44") (pintype "passive"))
    )
    (net (code "56") (name "/GPIO47") (class "Default")
      (node (ref "J2") (pin "23") (pinfunction "23_23") (pintype "passive"))
      (node (ref "U1") (pin "27") (pinfunction "GPIO47/SPICLK_P_DIFF/SUBSPICLK_P_DIFF_27") (pintype "passive"))
    )
    (net (code "57") (name "/GPIO48") (class "Default")
      (node (ref "J2") (pin "22") (pinfunction "22_22") (pintype "passive"))
      (node (ref "U1") (pin "30") (pinfunction "GPIO48/SPICLK_N_DIFF/SUBSPICLK_N_DIFF_30") (pintype "passive"))
    )
    (net (code "58") (name "/RTS_FTDI") (class "Default")
      (node (ref "Q1") (pin "2") (pinfunction "E_2") (pintype "passive"))
      (node (ref "R21") (pin "1") (pinfunction "1_1") (pintype "passive"))
      (node (ref "U2") (pin "19") (pinfunction "~{RTS}_19") (pintype "passive"))
    )
    (net (code "59") (name "/RXD_FTDI") (class "Default")
      (node (ref "R19") (pin "2") (pinfunction "2_2") (pintype "passive"))
      (node (ref "U2") (pin "1") (pinfunction "RXD_1") (pintype "passive"))
    )
    (net (code "60") (name "/TXD_FTDI") (class "Default")
      (node (ref "R30") (pin "2") (pinfunction "2_2") (pintype "passive"))
      (node (ref "U2") (pin "17") (pinfunction "TXD_17") (pintype "passive"))
    )
    (net (code "61") (name "/U0RXD") (class "Default")
      (node (ref "J2") (pin "6") (pinfunction "6_6") (pintype "passive"))
      (node (ref "R30") (pin "1") (pinfunction "1_1") (pintype "passive"))
      (node (ref "U1") (pin "40") (pinfunction "U0RXD/GPIO44/CLK_OUT2_40") (pintype "passive"))
    )
    (net (code "62") (name "/U0TXD") (class "Default")
      (node (ref "J2") (pin "7") (pinfunction "7_7") (pintype "passive"))
      (node (ref "R19") (pin "1") (pinfunction "1_1") (pintype "passive"))
      (node (ref "U1") (pin "39") (pinfunction "U0TXD/GPIO43/CLK_OUT1_39") (pintype "passive"))
    )
    (net (code "63") (name "/VBUS_SENSE") (class "Default")
      (node (ref "R13") (pin "1") (pinfunction "1_1") (pintype "passive"))
      (node (ref "R9") (pin "2") (pinfunction "2_2") (pintype "passive"))
      (node (ref "U2") (pin "16") (pinfunction "CBUS3_16") (pintype "passive"))
    )
    (net (code "64") (name "GND") (class "Default")
      (node (ref "C1") (pin "2") (pinfunction "2_2") (pintype "passive"))
      (node (ref "C10") (pin "1") (pinfunction "1_1") (pintype "passive"))
      (node (ref "C11") (pin "2") (pinfunction "2_2") (pintype "passive"))
      (node (ref "C12") (pin "2") (pinfunction "2_2") (pintype "passive"))
      (node (ref "C13") (pin "2") (pinfunction "2_2") (pintype "passive"))
      (node (ref "C14") (pin "2") (pinfunction "2_2") (pintype "passive"))
      (node (ref "C15") (pin "2") (pinfunction "2_2") (pintype "passive"))
      (node (ref "C16") (pin "1") (pinfunction "1_1") (pintype "passive"))
      (node (ref "C17") (pin "2") (pinfunction "2_2") (pintype "passive"))
      (node (ref "C2") (pin "2") (pinfunction "2_2") (pintype "passive"))
      (node (ref "C3") (pin "2") (pinfunction "2_2") (pintype "passive"))
      (node (ref "C4") (pin "1") (pinfunction "1_1") (pintype "passive"))
      (node (ref "C5") (pin "2") (pinfunction "2_2") (pintype "passive"))
      (node (ref "C6") (pin "2") (pinfunction "2_2") (pintype "passive"))
      (node (ref "C7") (pin "2") (pinfunction "2_2") (pintype "passive"))
      (node (ref "C8") (pin "2") (pinfunction "2_2") (pintype "passive"))
      (node (ref "C9") (pin "2") (pinfunction "2_2") (pintype "passive"))
      (node (ref "D1") (pin "1") (pinfunction "1_1") (pintype "passive"))
      (node (ref "D3") (pin "1") (pinfunction "1_1") (pintype "passive"))
      (node (ref "D4") (pin "1") (pinfunction "1_1") (pintype "passive"))
      (node (ref "D5") (pin "1") (pinfunction "1_1") (pintype "passive"))
      (node (ref "D6") (pin "1") (pinfunction "1_1") (pintype "passive"))
      (node (ref "D7") (pin "1") (pinfunction "1_1") (pintype "passive"))
      (node (ref "D8") (pin "1") (pinfunction "1_1") (pintype "passive"))
      (node (ref "J1") (pin "1") (pinfunction "1_1") (pintype "passive"))
      (node (ref "J1") (pin "23") (pinfunction "23_23") (pintype "passive"))
      (node (ref "J2") (pin "2") (pinfunction "2_2") (pintype "passive"))
      (node (ref "J2") (pin "24") (pinfunction "24_24") (pintype "passive"))
      (node (ref "J3") (pin "A1B12") (pinfunction "GND_A1B12_A1B12") (pintype "passive"))
      (node (ref "J3") (pin "B1A12") (pinfunction "GND_B4A9_B1A12") (pintype "passive"))
      (node (ref "J3") (pin "S1") (pinfunction "SHIELD_1_S1") (pintype "passive"))
      (node (ref "J3") (pin "S2") (pinfunction "SHIELD_2_S2") (pintype "passive"))
      (node (ref "J3") (pin "S3") (pinfunction "SHIELD_3_S3") (pintype "passive"))
      (node (ref "J3") (pin "S4") (pinfunction "SHIELD_4_S4") (pintype "passive"))
      (node (ref "J4") (pin "A1B12") (pinfunction "GND_A1B12_A1B12") (pintype "passive"))
      (node (ref "J4") (pin "B1A12") (pinfunction "GND_B4A9_B1A12") (pintype "passive"))
      (node (ref "J4") (pin "S1") (pinfunction "SHIELD_1_S1") (pintype "passive"))
      (node (ref "J4") (pin "S2") (pinfunction "SHIELD_2_S2") (pintype "passive"))
      (node (ref "J4") (pin "S3") (pinfunction "SHIELD_3_S3") (pintype "passive"))
      (node (ref "J4") (pin "S4") (pinfunction "SHIELD_4_S4") (pintype "passive"))
      (node (ref "R10") (pin "2") (pinfunction "2_2") (pintype "passive"))
      (node (ref "R11") (pin "1") (pinfunction "1_1") (pintype "passive"))
      (node (ref "R12") (pin "1") (pinfunction "1_1") (pintype "passive"))
      (node (ref "R13") (pin "2") (pinfunction "2_2") (pintype "passive"))
      (node (ref "R14") (pin "1") (pinfunction "1_1") (pintype "passive"))
      (node (ref "R15") (pin "1") (pinfunction "1_1") (pintype "passive"))
      (node (ref "SW1") (pin "3") (pinfunction "3_3") (pintype "passive"))
      (node (ref "SW1") (pin "4") (pinfunction "4_4") (pintype "passive"))
      (node (ref "SW2") (pin "3") (pinfunction "3_3") (pintype "passive"))
      (node (ref "SW2") (pin "4") (pinfunction "4_4") (pintype "passive"))
      (node (ref "U1") (pin "1") (pinfunction "GND_01_1") (pintype "passive"))
      (node (ref "U1") (pin "2") (pinfunction "GND_02_2") (pintype "passive"))
      (node (ref "U1") (pin "42") (pinfunction "GND_42") (pintype "passive"))
      (node (ref "U1") (pin "43") (pinfunction "GND_43") (pintype "passive"))
      (node (ref "U1") (pin "46") (pinfunction "GND_46_46") (pintype "passive"))
      (node (ref "U1") (pin "47") (pinfunction "GND_47_47") (pintype "passive"))
      (node (ref "U1") (pin "48") (pinfunction "GND_48_48") (pintype "passive"))
      (node (ref "U1") (pin "49") (pinfunction "GND_49_49") (pintype "passive"))
      (node (ref "U1") (pin "50") (pinfunction "GND_50_50") (pintype "passive"))
      (node (ref "U1") (pin "51") (pinfunction "GND_51_51") (pintype "passive"))
      (node (ref "U1") (pin "52") (pinfunction "GND_52_52") (pintype "passive"))
      (node (ref "U1") (pin "53") (pinfunction "GND_53_53") (pintype "passive"))
      (node (ref "U1") (pin "54") (pinfunction "GND_54_54") (pintype "passive"))
      (node (ref "U1") (pin "55") (pinfunction "GND_55_55") (pintype "passive"))
      (node (ref "U1") (pin "56") (pinfunction "GND_56_56") (pintype "passive"))
      (node (ref "U1") (pin "57") (pinfunction "GND_57_57") (pintype "passive"))
      (node (ref "U1") (pin "58") (pinfunction "GND_58_58") (pintype "passive"))
      (node (ref "U1") (pin "59") (pinfunction "GND_59_59") (pintype "passive"))
      (node (ref "U1") (pin "60") (pinfunction "GND_60_60") (pintype "passive"))
      (node (ref "U1") (pin "61") (pinfunction "GND_61_61") (pintype "passive"))
      (node (ref "U1") (pin "62") (pinfunction "GND_62_62") (pintype "passive"))
      (node (ref "U1") (pin "63") (pinfunction "GND_63_63") (pintype "passive"))
      (node (ref "U1") (pin "64") (pinfunction "GND_64_64") (pintype "passive"))
      (node (ref "U1") (pin "65") (pinfunction "GND_65_65") (pintype "passive"))
      (node (ref "U1") (pin "66") (pinfunction "GND_66_66") (pintype "passive"))
      (node (ref "U1") (pin "67") (pinfunction "GND_67_67") (pintype "passive"))
      (node (ref "U1") (pin "68") (pinfunction "GND_68_68") (pintype "passive"))
      (node (ref "U1") (pin "69") (pinfunction "GND_69_69") (pintype "passive"))
      (node (ref "U1") (pin "70") (pinfunction "GND_70_70") (pintype "passive"))
      (node (ref "U1") (pin "71") (pinfunction "GND_71_71") (pintype "passive"))
      (node (ref "U1") (pin "72") (pinfunction "GND_72_72") (pintype "passive"))
      (node (ref "U1") (pin "73") (pinfunction "GND_73_73") (pintype "passive"))
      (node (ref "U2") (pin "13") (pinfunction "GND_13") (pintype "passive"))
      (node (ref "U2") (pin "21") (pinfunction "GND_21") (pintype "passive"))
      (node (ref "U2") (pin "3") (pinfunction "GND_3") (pintype "passive"))
      (node (ref "U3") (pin "2") (pinfunction "GND_2") (pintype "power_in"))
      (node (ref "U3") (pin "4") (pinfunction "GND_4") (pintype "power_in"))
    )
    (net (code "65") (name "Net-(D1-Pad2)") (class "Default")
      (node (ref "D1") (pin "2") (pinfunction "2_2") (pintype "passive"))
      (node (ref "R3") (pin "1") (pinfunction "1_1") (pintype "passive"))
    )
    (net (code "66") (name "Net-(D2-Pad2)") (class "Default")
      (node (ref "D2") (pin "2") (pinfunction "2_2") (pintype "passive"))
      (node (ref "R4") (pin "1") (pinfunction "1_1") (pintype "passive"))
    )
    (net (code "67") (name "Net-(J3-CC1)") (class "Default")
      (node (ref "J3") (pin "A5") (pinfunction "CC1_A5") (pintype "passive"))
      (node (ref "R12") (pin "2") (pinfunction "2_2") (pintype "passive"))
    )
    (net (code "68") (name "Net-(J3-CC2)") (class "Default")
      (node (ref "J3") (pin "B5") (pinfunction "CC2_B5") (pintype "passive"))
      (node (ref "R11") (pin "2") (pinfunction "2_2") (pintype "passive"))
    )
    (net (code "69") (name "Net-(J4-CC1)") (class "Default")
      (node (ref "J4") (pin "A5") (pinfunction "CC1_A5") (pintype "passive"))
      (node (ref "R15") (pin "2") (pinfunction "2_2") (pintype "passive"))
    )
    (net (code "70") (name "Net-(J4-CC2)") (class "Default")
      (node (ref "J4") (pin "B5") (pinfunction "CC2_B5") (pintype "passive"))
      (node (ref "R14") (pin "2") (pinfunction "2_2") (pintype "passive"))
    )
    (net (code "71") (name "Net-(Q1-B)") (class "Default")
      (node (ref "Q1") (pin "1") (pinfunction "B_1") (pintype "passive"))
      (node (ref "R16") (pin "2") (pinfunction "2_2") (pintype "passive"))
    )
    (net (code "72") (name "Net-(Q2-B)") (class "Default")
      (node (ref "Q2") (pin "1") (pinfunction "B_1") (pintype "passive"))
      (node (ref "R21") (pin "2") (pinfunction "2_2") (pintype "passive"))
    )
    (net (code "73") (name "Net-(U2-CBUS0)") (class "Default")
      (node (ref "R10") (pin "1") (pinfunction "1_1") (pintype "passive"))
      (node (ref "U2") (pin "15") (pinfunction "CBUS0_15") (pintype "passive"))
    )
    (net (code "74") (name "unconnected-(J1-Pad24)") (class "Default")
      (node (ref "J1") (pin "24") (pinfunction "24_24") (pintype "passive+no_connect"))
    )
    (net (code "75") (name "unconnected-(J3-SBU1-PadA8)") (class "Default")
      (node (ref "J3") (pin "A8") (pinfunction "SBU1_A8") (pintype "passive+no_connect"))
    )
    (net (code "76") (name "unconnected-(J3-SBU2-PadB8)") (class "Default")
      (node (ref "J3") (pin "B8") (pinfunction "SBU2_B8") (pintype "passive+no_connect"))
    )
    (net (code "77") (name "unconnected-(J4-SBU1-PadA8)") (class "Default")
      (node (ref "J4") (pin "A8") (pinfunction "SBU1_A8") (pintype "passive+no_connect"))
    )
    (net (code "78") (name "unconnected-(J4-SBU2-PadB8)") (class "Default")
      (node (ref "J4") (pin "B8") (pinfunction "SBU2_B8") (pintype "passive+no_connect"))
    )
    (net (code "79") (name "unconnected-(U2-CBUS1-Pad14)") (class "Default")
      (node (ref "U2") (pin "14") (pinfunction "CBUS1_14") (pintype "passive+no_connect"))
    )
    (net (code "80") (name "unconnected-(U2-CBUS2-Pad7)") (class "Default")
      (node (ref "U2") (pin "7") (pinfunction "CBUS2_7") (pintype "passive+no_connect"))
    )
    (net (code "81") (name "unconnected-(U2-~{CTS}-Pad6)") (class "Default")
      (node (ref "U2") (pin "6") (pinfunction "~{CTS}_6") (pintype "passive"))
    )
    (net (code "82") (name "unconnected-(U2-~{DCD}-Pad5)") (class "Default")
      (node (ref "U2") (pin "5") (pinfunction "~{DCD}_5") (pintype "passive"))
    )
    (net (code "83") (name "unconnected-(U2-~{DSR}-Pad4)") (class "Default")
      (node (ref "U2") (pin "4") (pinfunction "~{DSR}_4") (pintype "passive"))
    )
    (net (code "84") (name "unconnected-(U2-~{RI}-Pad2)") (class "Default")
      (node (ref "U2") (pin "2") (pinfunction "~{RI}_2") (pintype "passive"))
    )
  )
)
